# Pit-RFD.net
KiCad netlist of a schematic drawn in Altium Designer
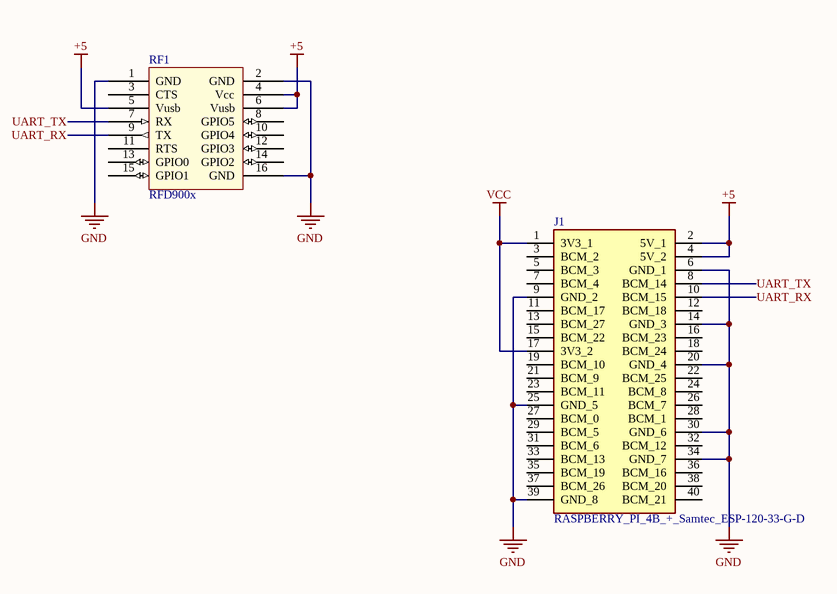
[diagram p0: Pit-RFD.SchDoc]

(export (version "E")
  (design (tool "Eeschema 10.0.6"))
  (components
    (comp (ref "J1")
      (value "RASPBERRY_PI_4B_+_Samtec_ESP-120-33-G-D")
      (footprint "SamacSys:RASPBERRYPI4B4GB")
      (description "Connector")
      (fields (field (name "MANUFACTURER_PART_NUMBER") "RASPBERRY PI 4B + Samtec ESP-120-33-G-D"))
      (libsource (lib "*") (part "RASPBERRY_PI_4B_+_Samtec_ESP-120-33-G-D"))
    )
    (comp (ref "RF1")
      (value "RFD900x")
      (footprint "RFD900X_HS_U")
      (libsource (lib "RFD900x") (part "RFD900x"))
    )
  )
  (nets
    (net (code "1") (name "+5") (class "Default")
      (node (ref "J1") (pin "2") (pinfunction "5V_1_2") (pintype "power_in"))
      (node (ref "J1") (pin "4") (pinfunction "5V_2_4") (pintype "power_in"))
      (node (ref "RF1") (pin "4") (pinfunction "Vcc_4") (pintype "power_in"))
      (node (ref "RF1") (pin "5") (pinfunction "Vusb_5") (pintype "power_in"))
      (node (ref "RF1") (pin "6") (pinfunction "Vusb_6") (pintype "power_in"))
    )
    (net (code "2") (name "/UART_RX") (class "Default")
      (node (ref "J1") (pin "10") (pinfunction "BCM_15_10") (pintype "passive"))
      (node (ref "RF1") (pin "9") (pinfunction "TX_9") (pintype "output"))
    )
    (net (code "3") (name "/UART_TX") (class "Default")
      (node (ref "J1") (pin "8") (pinfunction "BCM_14_8") (pintype "passive"))
      (node (ref "RF1") (pin "7") (pinfunction "RX_7") (pintype "input"))
    )
    (net (code "4") (name "GND") (class "Default")
      (node (ref "J1") (pin "14") (pinfunction "GND_3_14") (pintype "power_in"))
      (node (ref "J1") (pin "20") (pinfunction "GND_4_20") (pintype "power_in"))
      (node (ref "J1") (pin "25") (pinfunction "GND_5_25") (pintype "power_in"))
      (node (ref "J1") (pin "30") (pinfunction "GND_6_30") (pintype "power_in"))
      (node (ref "J1") (pin "34") (pinfunction "GND_7_34") (pintype "power_in"))
      (node (ref "J1") (pin "39") (pinfunction "GND_8_39") (pintype "power_in"))
      (node (ref "J1") (pin "6") (pinfunction "GND_1_6") (pintype "power_in"))
      (node (ref "J1") (pin "9") (pinfunction "GND_2_9") (pintype "power_in"))
      (node (ref "RF1") (pin "1") (pinfunction "GND_1") (pintype "passive"))
      (node (ref "RF1") (pin "16") (pinfunction "GND_16") (pintype "passive"))
      (node (ref "RF1") (pin "2") (pinfunction "GND_2") (pintype "passive"))
    )
    (net (code "5") (name "VCC") (class "Default")
      (node (ref "J1") (pin "1") (pinfunction "3V3_1_1") (pintype "power_in"))
      (node (ref "J1") (pin "17") (pinfunction "3V3_2_17") (pintype "power_in"))
    )
    (net (code "6") (name "unconnected-(J1-BCM_0-Pad27)") (class "Default")
      (node (ref "J1") (pin "27") (pinfunction "BCM_0_27") (pintype "passive"))
    )
    (net (code "7") (name "unconnected-(J1-BCM_1-Pad28)") (class "Default")
      (node (ref "J1") (pin "28") (pinfunction "BCM_1_28") (pintype "passive"))
    )
    (net (code "8") (name "unconnected-(J1-BCM_2-Pad3)") (class "Default")
      (node (ref "J1") (pin "3") (pinfunction "BCM_2_3") (pintype "passive"))
    )
    (net (code "9") (name "unconnected-(J1-BCM_3-Pad5)") (class "Default")
      (node (ref "J1") (pin "5") (pinfunction "BCM_3_5") (pintype "passive"))
    )
    (net (code "10") (name "unconnected-(J1-BCM_4-Pad7)") (class "Default")
      (node (ref "J1") (pin "7") (pinfunction "BCM_4_7") (pintype "passive"))
    )
    (net (code "11") (name "unconnected-(J1-BCM_5-Pad29)") (class "Default")
      (node (ref "J1") (pin "29") (pinfunction "BCM_5_29") (pintype "passive"))
    )
    (net (code "12") (name "unconnected-(J1-BCM_6-Pad31)") (class "Default")
      (node (ref "J1") (pin "31") (pinfunction "BCM_6_31") (pintype "passive"))
    )
    (net (code "13") (name "unconnected-(J1-BCM_7-Pad26)") (class "Default")
      (node (ref "J1") (pin "26") (pinfunction "BCM_7_26") (pintype "passive"))
    )
    (net (code "14") (name "unconnected-(J1-BCM_8-Pad24)") (class "Default")
      (node (ref "J1") (pin "24") (pinfunction "BCM_8_24") (pintype "passive"))
    )
    (net (code "15") (name "unconnected-(J1-BCM_9-Pad21)") (class "Default")
      (node (ref "J1") (pin "21") (pinfunction "BCM_9_21") (pintype "passive"))
    )
    (net (code "16") (name "unconnected-(J1-BCM_10-Pad19)") (class "Default")
      (node (ref "J1") (pin "19") (pinfunction "BCM_10_19") (pintype "passive"))
    )
    (net (code "17") (name "unconnected-(J1-BCM_11-Pad23)") (class "Default")
      (node (ref "J1") (pin "23") (pinfunction "BCM_11_23") (pintype "passive"))
    )
    (net (code "18") (name "unconnected-(J1-BCM_12-Pad32)") (class "Default")
      (node (ref "J1") (pin "32") (pinfunction "BCM_12_32") (pintype "passive"))
    )
    (net (code "19") (name "unconnected-(J1-BCM_13-Pad33)") (class "Default")
      (node (ref "J1") (pin "33") (pinfunction "BCM_13_33") (pintype "passive"))
    )
    (net (code "20") (name "unconnected-(J1-BCM_16-Pad36)") (class "Default")
      (node (ref "J1") (pin "36") (pinfunction "BCM_16_36") (pintype "passive"))
    )
    (net (code "21") (name "unconnected-(J1-BCM_17-Pad11)") (class "Default")
      (node (ref "J1") (pin "11") (pinfunction "BCM_17_11") (pintype "passive"))
    )
    (net (code "22") (name "unconnected-(J1-BCM_18-Pad12)") (class "Default")
      (node (ref "J1") (pin "12") (pinfunction "BCM_18_12") (pintype "passive"))
    )
    (net (code "23") (name "unconnected-(J1-BCM_19-Pad35)") (class "Default")
      (node (ref "J1") (pin "35") (pinfunction "BCM_19_35") (pintype "passive"))
    )
    (net (code "24") (name "unconnected-(J1-BCM_20-Pad38)") (class "Default")
      (node (ref "J1") (pin "38") (pinfunction "BCM_20_38") (pintype "passive"))
    )
    (net (code "25") (name "unconnected-(J1-BCM_21-Pad40)") (class "Default")
      (node (ref "J1") (pin "40") (pinfunction "BCM_21_40") (pintype "passive"))
    )
    (net (code "26") (name "unconnected-(J1-BCM_22-Pad15)") (class "Default")
      (node (ref "J1") (pin "15") (pinfunction "BCM_22_15") (pintype "passive"))
    )
    (net (code "27") (name "unconnected-(J1-BCM_23-Pad16)") (class "Default")
      (node (ref "J1") (pin "16") (pinfunction "BCM_23_16") (pintype "passive"))
    )
    (net (code "28") (name "unconnected-(J1-BCM_24-Pad18)") (class "Default")
      (node (ref "J1") (pin "18") (pinfunction "BCM_24_18") (pintype "passive"))
    )
    (net (code "29") (name "unconnected-(J1-BCM_25-Pad22)") (class "Default")
      (node (ref "J1") (pin "22") (pinfunction "BCM_25_22") (pintype "passive"))
    )
    (net (code "30") (name "unconnected-(J1-BCM_26-Pad37)") (class "Default")
      (node (ref "J1") (pin "37") (pinfunction "BCM_26_37") (pintype "passive"))
    )
    (net (code "31") (name "unconnected-(J1-BCM_27-Pad13)") (class "Default")
      (node (ref "J1") (pin "13") (pinfunction "BCM_27_13") (pintype "passive"))
    )
    (net (code "32") (name "unconnected-(RF1-CTS-Pad3)") (class "Default")
      (node (ref "RF1") (pin "3") (pinfunction "CTS_3") (pintype "passive"))
    )
    (net (code "33") (name "unconnected-(RF1-GPIO0-Pad13)") (class "Default")
      (node (ref "RF1") (pin "13") (pinfunction "GPIO0_13") (pintype "bidirectional"))
    )
    (net (code "34") (name "unconnected-(RF1-GPIO1-Pad15)") (class "Default")
      (node (ref "RF1") (pin "15") (pinfunction "GPIO1_15") (pintype "bidirectional"))
    )
    (net (code "35") (name "unconnected-(RF1-GPIO2-Pad14)") (class "Default")
      (node (ref "RF1") (pin "14") (pinfunction "GPIO2_14") (pintype "bidirectional"))
    )
    (net (code "36") (name "unconnected-(RF1-GPIO3-Pad12)") (class "Default")
      (node (ref "RF1") (pin "12") (pinfunction "GPIO3_12") (pintype "bidirectional"))
    )
    (net (code "37") (name "unconnected-(RF1-GPIO4-Pad10)") (class "Default")
      (node (ref "RF1") (pin "10") (pinfunction "GPIO4_10") (pintype "bidirectional"))
    )
    (net (code "38") (name "unconnected-(RF1-GPIO5-Pad8)") (class "Default")
      (node (ref "RF1") (pin "8") (pinfunction "GPIO5_8") (pintype "bidirectional"))
    )
    (net (code "39") (name "unconnected-(RF1-RTS-Pad11)") (class "Default")
      (node (ref "RF1") (pin "11") (pinfunction "RTS_11") (pintype "passive"))
    )
  )
)
